# 1_Sheet_1.net
KiCad netlist of a schematic drawn in Altium Designer
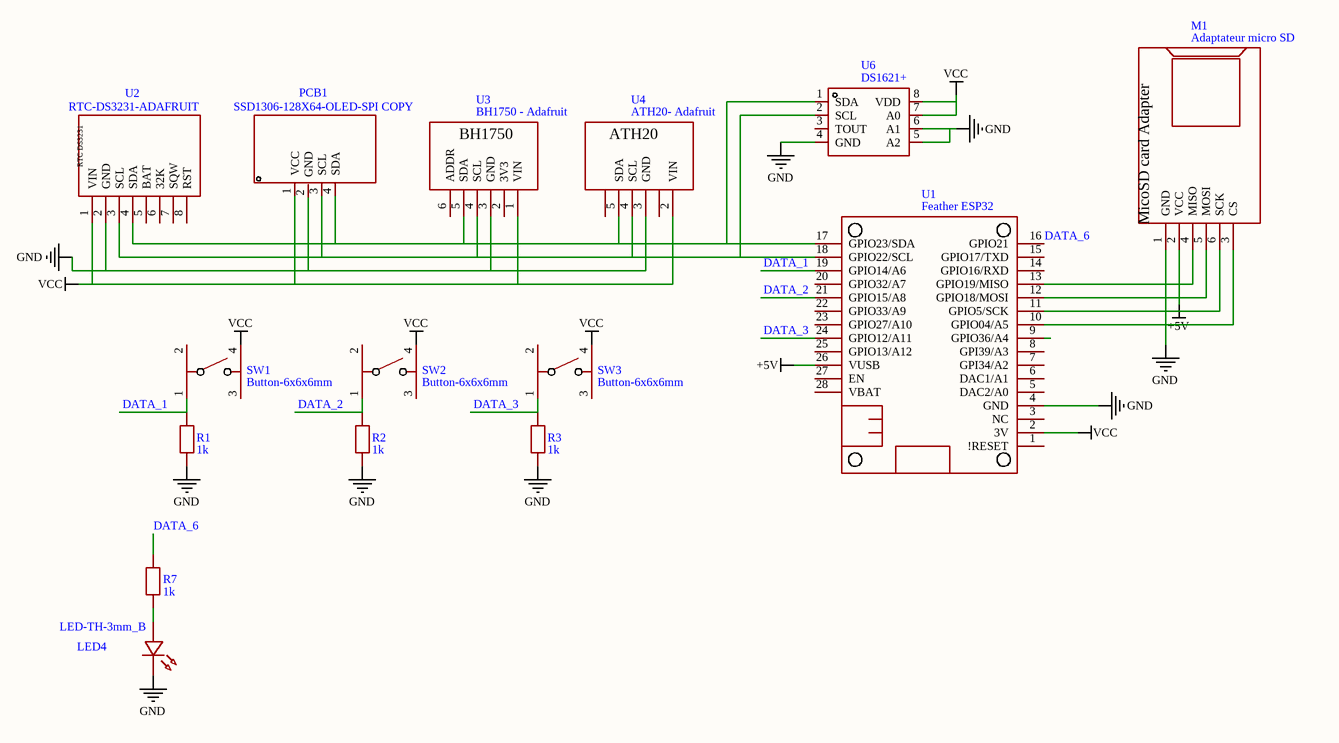
[diagram p0: 1_Sheet_1.schdoc]

(export (version "E")
  (design (tool "Eeschema 10.0.6"))
  (components
    (comp (ref "LED4")
      (value "LED-TH-3mm_B")
      (footprint "LED-TH_BD3.0_BLUE")
      (fields
        (field (name "MANUFACTURER") "EVERLIGHT(台湾亿光)")
        (field (name "MANUFACTURER PART") "204-10SUBC/S400-A4")
        (field (name "CONTRIBUTOR") "LCEDA_Lib")
      )
      (libsource (lib "altium-import") (part "root_3_LED-TH-3mm_B_"))
    )
    (comp (ref "M1")
      (value "Adaptateur micro SD")
      (footprint "MICROSD_ADAPTER_BOARD")
      (fields (field (name "CONTRIBUTOR") "LTG Tech"))
      (libsource (lib "altium-import") (part "root_3_Adaptateur micro SD_"))
    )
    (comp (ref "PCB1")
      (value "SSD1306-128X64-OLED-SPI COPY")
      (footprint "SSD1306")
      (libsource (lib "altium-import") (part "root_1_SSD1306-128X64-OLED-SPI COPY_"))
    )
    (comp (ref "R1")
      (value "1k")
      (footprint "R_AXIAL-0.4")
      (fields (field (name "CONTRIBUTOR") "LCEDA_Lib"))
      (libsource (lib "altium-import") (part "root_3_1k_"))
    )
    (comp (ref "R2")
      (value "1k")
      (footprint "R_AXIAL-0.4")
      (fields (field (name "CONTRIBUTOR") "LCEDA_Lib"))
      (libsource (lib "altium-import") (part "root_3_1k_"))
    )
    (comp (ref "R3")
      (value "1k")
      (footprint "R_AXIAL-0.4")
      (fields (field (name "CONTRIBUTOR") "LCEDA_Lib"))
      (libsource (lib "altium-import") (part "root_3_1k_"))
    )
    (comp (ref "R7")
      (value "1k")
      (footprint "R_AXIAL-0.4")
      (fields (field (name "CONTRIBUTOR") "LCEDA_Lib"))
      (libsource (lib "altium-import") (part "root_1_1k_"))
    )
    (comp (ref "SW1")
      (value "Button-6x6x6mm")
      (footprint "SW-TH_4P-L6.0-W6.0-P4.50-LS6.1")
      (fields
        (field (name "MANUFACTURER") "BBJ")
        (field (name "MANUFACTURER PART") "Switch,6*6*6Plastic head,260G, 0.25mm,Straight line")
      )
      (libsource (lib "altium-import") (part "root_1_Button-6x6x6mm_"))
    )
    (comp (ref "SW2")
      (value "Button-6x6x6mm")
      (footprint "SW-TH_4P-L6.0-W6.0-P4.50-LS6.1")
      (fields
        (field (name "MANUFACTURER") "BBJ")
        (field (name "MANUFACTURER PART") "Switch,6*6*6Plastic head,260G, 0.25mm,Straight line")
      )
      (libsource (lib "altium-import") (part "root_1_Button-6x6x6mm_"))
    )
    (comp (ref "SW3")
      (value "Button-6x6x6mm")
      (footprint "SW-TH_4P-L6.0-W6.0-P4.50-LS6.1")
      (fields
        (field (name "MANUFACTURER") "BBJ")
        (field (name "MANUFACTURER PART") "Switch,6*6*6Plastic head,260G, 0.25mm,Straight line")
      )
      (libsource (lib "altium-import") (part "root_1_Button-6x6x6mm_"))
    )
    (comp (ref "U1")
      (value "Feather ESP32")
      (footprint "ADAFRUIT FEATHER ESP32")
      (fields (field (name "CONTRIBUTOR") "kristylynn9598"))
      (libsource (lib "altium-import") (part "root_2_Feather ESP32_"))
    )
    (comp (ref "U2")
      (value "RTC-DS3231-ADAFRUIT")
      (footprint "RTC-DS3231-ADAFRUIT")
      (fields (field (name "MANUFACTURER") "ADAFRUIT") (field (name "CONTRIBUTOR") "JEEn"))
      (libsource (lib "altium-import") (part "root_1_RTC-DS3231-ADAFRUIT_"))
    )
    (comp (ref "U3")
      (value "BH1750 - Adafruit")
      (footprint "BH1750 - ADAFRUIT")
      (fields (field (name "CONTRIBUTOR") "mengrie"))
      (libsource (lib "altium-import") (part "root_3_BH1750 - Adafruit_"))
    )
    (comp (ref "U4")
      (value "ATH20- Adafruit")
      (footprint "BH1750 - ADAFRUIT")
      (fields (field (name "CONTRIBUTOR") "mengrie"))
      (libsource (lib "altium-import") (part "root_3_ATH20- Adafruit_"))
    )
    (comp (ref "U6")
      (value "DS1621+")
      (footprint "DIP-8_L9.8-W6.6-P2.54-LS7.6-BL")
      (fields (field (name "MANUFACTURER") "ADI(亚德诺)/MAXIM(美信)") (field (name "CONTRIBUTOR") "LCSC"))
      (libsource (lib "altium-import") (part "root_0_DS1621+_"))
    )
  )
  (nets
    (net (code "1") (name "+5V") (class "Default")
      (node (ref "M1") (pin "2") (pinfunction "VCC_2") (pintype "passive"))
      (node (ref "U1") (pin "26") (pinfunction "VUSB_26") (pintype "passive"))
    )
    (net (code "2") (name "/DATA_1") (class "Default")
      (node (ref "R1") (pin "1") (pinfunction "1_1") (pintype "passive"))
      (node (ref "SW1") (pin "1") (pinfunction "1_1") (pintype "passive"))
      (node (ref "U1") (pin "19") (pinfunction "GPIO14/A6_19") (pintype "passive"))
    )
    (net (code "3") (name "/DATA_2") (class "Default")
      (node (ref "R2") (pin "1") (pinfunction "1_1") (pintype "passive"))
      (node (ref "SW2") (pin "1") (pinfunction "1_1") (pintype "passive"))
      (node (ref "U1") (pin "21") (pinfunction "GPIO15/A8_21") (pintype "passive"))
    )
    (net (code "4") (name "/DATA_3") (class "Default")
      (node (ref "R3") (pin "1") (pinfunction "1_1") (pintype "passive"))
      (node (ref "SW3") (pin "1") (pinfunction "1_1") (pintype "passive"))
      (node (ref "U1") (pin "24") (pinfunction "GPIO12/A11_24") (pintype "passive"))
    )
    (net (code "5") (name "/DATA_6") (class "Default")
      (node (ref "R7") (pin "2") (pinfunction "2_2") (pintype "passive"))
      (node (ref "U1") (pin "16") (pinfunction "GPIO21_16") (pintype "passive"))
    )
    (net (code "6") (name "GND") (class "Default")
      (node (ref "LED4") (pin "2") (pinfunction "2_2") (pintype "passive"))
      (node (ref "M1") (pin "1") (pinfunction "GND_1") (pintype "passive"))
      (node (ref "PCB1") (pin "2") (pinfunction "GND_2") (pintype "passive"))
      (node (ref "R1") (pin "2") (pinfunction "2_2") (pintype "passive"))
      (node (ref "R2") (pin "2") (pinfunction "2_2") (pintype "passive"))
      (node (ref "R3") (pin "2") (pinfunction "2_2") (pintype "passive"))
      (node (ref "U1") (pin "4") (pinfunction "GND_4") (pintype "passive"))
      (node (ref "U2") (pin "2") (pinfunction "GND_2") (pintype "passive"))
      (node (ref "U3") (pin "3") (pinfunction "GND_3") (pintype "passive"))
      (node (ref "U4") (pin "3") (pinfunction "GND_3") (pintype "passive"))
      (node (ref "U6") (pin "4") (pinfunction "GND_4") (pintype "passive"))
      (node (ref "U6") (pin "5") (pinfunction "A2_5") (pintype "passive"))
      (node (ref "U6") (pin "6") (pinfunction "A1_6") (pintype "passive"))
    )
    (net (code "7") (name "Net-(LED4-Pad1)") (class "Default")
      (node (ref "LED4") (pin "1") (pinfunction "1_1") (pintype "passive"))
      (node (ref "R7") (pin "1") (pinfunction "1_1") (pintype "passive"))
    )
    (net (code "8") (name "Net-(M1-CS)") (class "Default")
      (node (ref "M1") (pin "3") (pinfunction "CS_3") (pintype "passive"))
      (node (ref "U1") (pin "10") (pinfunction "GPIO04/A5_10") (pintype "passive"))
    )
    (net (code "9") (name "Net-(M1-MISO)") (class "Default")
      (node (ref "M1") (pin "4") (pinfunction "MISO_4") (pintype "passive"))
      (node (ref "U1") (pin "13") (pinfunction "GPIO19/MISO_13") (pintype "passive"))
    )
    (net (code "10") (name "Net-(M1-MOSI)") (class "Default")
      (node (ref "M1") (pin "5") (pinfunction "MOSI_5") (pintype "passive"))
      (node (ref "U1") (pin "12") (pinfunction "GPIO18/MOSI_12") (pintype "passive"))
    )
    (net (code "11") (name "Net-(M1-SCK)") (class "Default")
      (node (ref "M1") (pin "6") (pinfunction "SCK_6") (pintype "passive"))
      (node (ref "U1") (pin "11") (pinfunction "GPIO5/SCK_11") (pintype "passive"))
    )
    (net (code "12") (name "Net-(PCB1-SCL)") (class "Default")
      (node (ref "PCB1") (pin "3") (pinfunction "SCL_3") (pintype "passive"))
      (node (ref "U1") (pin "18") (pinfunction "GPIO22/SCL_18") (pintype "passive"))
      (node (ref "U2") (pin "3") (pinfunction "SCL_3") (pintype "passive"))
      (node (ref "U3") (pin "4") (pinfunction "SCL_4") (pintype "passive"))
      (node (ref "U4") (pin "4") (pinfunction "SCL_4") (pintype "passive"))
      (node (ref "U6") (pin "2") (pinfunction "SCL_2") (pintype "passive"))
    )
    (net (code "13") (name "Net-(PCB1-SDA)") (class "Default")
      (node (ref "PCB1") (pin "4") (pinfunction "SDA_4") (pintype "passive"))
      (node (ref "U1") (pin "17") (pinfunction "GPIO23/SDA_17") (pintype "passive"))
      (node (ref "U2") (pin "4") (pinfunction "SDA_4") (pintype "passive"))
      (node (ref "U3") (pin "5") (pinfunction "SDA_5") (pintype "passive"))
      (node (ref "U4") (pin "5") (pinfunction "SDA_5") (pintype "passive"))
      (node (ref "U6") (pin "1") (pinfunction "SDA_1") (pintype "passive"))
    )
    (net (code "14") (name "VCC") (class "Default")
      (node (ref "PCB1") (pin "1") (pinfunction "VCC_1") (pintype "passive"))
      (node (ref "SW1") (pin "4") (pinfunction "4_4") (pintype "passive"))
      (node (ref "SW2") (pin "4") (pinfunction "4_4") (pintype "passive"))
      (node (ref "SW3") (pin "4") (pinfunction "4_4") (pintype "passive"))
      (node (ref "U1") (pin "2") (pinfunction "3V_2") (pintype "passive"))
      (node (ref "U2") (pin "1") (pinfunction "VIN_1") (pintype "passive"))
      (node (ref "U3") (pin "1") (pinfunction "VIN_1") (pintype "passive"))
      (node (ref "U4") (pin "2") (pinfunction "VIN_2") (pintype "passive"))
      (node (ref "U6") (pin "7") (pinfunction "A0_7") (pintype "passive"))
      (node (ref "U6") (pin "8") (pinfunction "VDD_8") (pintype "passive"))
    )
    (net (code "15") (name "unconnected-(SW1-Pad2)") (class "Default")
      (node (ref "SW1") (pin "2") (pinfunction "2_2") (pintype "passive"))
    )
    (net (code "16") (name "unconnected-(SW1-Pad3)") (class "Default")
      (node (ref "SW1") (pin "3") (pinfunction "3_3") (pintype "passive"))
    )
    (net (code "17") (name "unconnected-(SW2-Pad2)") (class "Default")
      (node (ref "SW2") (pin "2") (pinfunction "2_2") (pintype "passive"))
    )
    (net (code "18") (name "unconnected-(SW2-Pad3)") (class "Default")
      (node (ref "SW2") (pin "3") (pinfunction "3_3") (pintype "passive"))
    )
    (net (code "19") (name "unconnected-(SW3-Pad2)") (class "Default")
      (node (ref "SW3") (pin "2") (pinfunction "2_2") (pintype "passive"))
    )
    (net (code "20") (name "unconnected-(SW3-Pad3)") (class "Default")
      (node (ref "SW3") (pin "3") (pinfunction "3_3") (pintype "passive"))
    )
    (net (code "21") (name "unconnected-(U1-!RESET-Pad1)") (class "Default")
      (node (ref "U1") (pin "1") (pinfunction "!RESET_1") (pintype "passive"))
    )
    (net (code "22") (name "unconnected-(U1-DAC1{slash}A1-Pad6)") (class "Default")
      (node (ref "U1") (pin "6") (pinfunction "DAC1/A1_6") (pintype "passive"))
    )
    (net (code "23") (name "unconnected-(U1-DAC2{slash}A0-Pad5)") (class "Default")
      (node (ref "U1") (pin "5") (pinfunction "DAC2/A0_5") (pintype "passive"))
    )
    (net (code "24") (name "unconnected-(U1-EN-Pad27)") (class "Default")
      (node (ref "U1") (pin "27") (pinfunction "EN_27") (pintype "passive"))
    )
    (net (code "25") (name "unconnected-(U1-GPI34{slash}A2-Pad7)") (class "Default")
      (node (ref "U1") (pin "7") (pinfunction "GPI34/A2_7") (pintype "passive"))
    )
    (net (code "26") (name "unconnected-(U1-GPI39{slash}A3-Pad8)") (class "Default")
      (node (ref "U1") (pin "8") (pinfunction "GPI39/A3_8") (pintype "passive"))
    )
    (net (code "27") (name "unconnected-(U1-GPIO13{slash}A12-Pad25)") (class "Default")
      (node (ref "U1") (pin "25") (pinfunction "GPIO13/A12_25") (pintype "passive"))
    )
    (net (code "28") (name "unconnected-(U1-GPIO16{slash}RXD-Pad14)") (class "Default")
      (node (ref "U1") (pin "14") (pinfunction "GPIO16/RXD_14") (pintype "passive"))
    )
    (net (code "29") (name "unconnected-(U1-GPIO17{slash}TXD-Pad15)") (class "Default")
      (node (ref "U1") (pin "15") (pinfunction "GPIO17/TXD_15") (pintype "passive"))
    )
    (net (code "30") (name "unconnected-(U1-GPIO27{slash}A10-Pad23)") (class "Default")
      (node (ref "U1") (pin "23") (pinfunction "GPIO27/A10_23") (pintype "passive"))
    )
    (net (code "31") (name "unconnected-(U1-GPIO32{slash}A7-Pad20)") (class "Default")
      (node (ref "U1") (pin "20") (pinfunction "GPIO32/A7_20") (pintype "passive"))
    )
    (net (code "32") (name "unconnected-(U1-GPIO33{slash}A9-Pad22)") (class "Default")
      (node (ref "U1") (pin "22") (pinfunction "GPIO33/A9_22") (pintype "passive"))
    )
    (net (code "33") (name "unconnected-(U1-GPIO36{slash}A4-Pad9)") (class "Default")
      (node (ref "U1") (pin "9") (pinfunction "GPIO36/A4_9") (pintype "passive"))
    )
    (net (code "34") (name "unconnected-(U1-NC-Pad3)") (class "Default")
      (node (ref "U1") (pin "3") (pinfunction "NC_3") (pintype "passive"))
    )
    (net (code "35") (name "unconnected-(U1-VBAT-Pad28)") (class "Default")
      (node (ref "U1") (pin "28") (pinfunction "VBAT_28") (pintype "passive"))
    )
    (net (code "36") (name "unconnected-(U2-32K-Pad6)") (class "Default")
      (node (ref "U2") (pin "6") (pinfunction "32K_6") (pintype "passive"))
    )
    (net (code "37") (name "unconnected-(U2-BAT-Pad5)") (class "Default")
      (node (ref "U2") (pin "5") (pinfunction "BAT_5") (pintype "passive"))
    )
    (net (code "38") (name "unconnected-(U2-RST-Pad8)") (class "Default")
      (node (ref "U2") (pin "8") (pinfunction "RST_8") (pintype "passive"))
    )
    (net (code "39") (name "unconnected-(U2-SQW-Pad7)") (class "Default")
      (node (ref "U2") (pin "7") (pinfunction "SQW_7") (pintype "passive"))
    )
    (net (code "40") (name "unconnected-(U3-3V3-Pad2)") (class "Default")
      (node (ref "U3") (pin "2") (pinfunction "3V3_2") (pintype "passive"))
    )
    (net (code "41") (name "unconnected-(U3-ADDR-Pad6)") (class "Default")
      (node (ref "U3") (pin "6") (pinfunction "ADDR_6") (pintype "passive"))
    )
    (net (code "42") (name "unconnected-(U4-3V3-Pad3)") (class "Default")
      (node (ref "U4") (pin "3") (pinfunction "3V3_3") (pintype "passive"))
    )
    (net (code "43") (name "unconnected-(U4-ADDR-Pad6)") (class "Default")
      (node (ref "U4") (pin "6") (pinfunction "ADDR_6") (pintype "passive"))
    )
    (net (code "44") (name "unconnected-(U6-TOUT-Pad3)") (class "Default")
      (node (ref "U6") (pin "3") (pinfunction "TOUT_3") (pintype "passive"))
    )
  )
)
